# Flyback_Schematic.net
KiCad netlist of a schematic drawn in Altium Designer
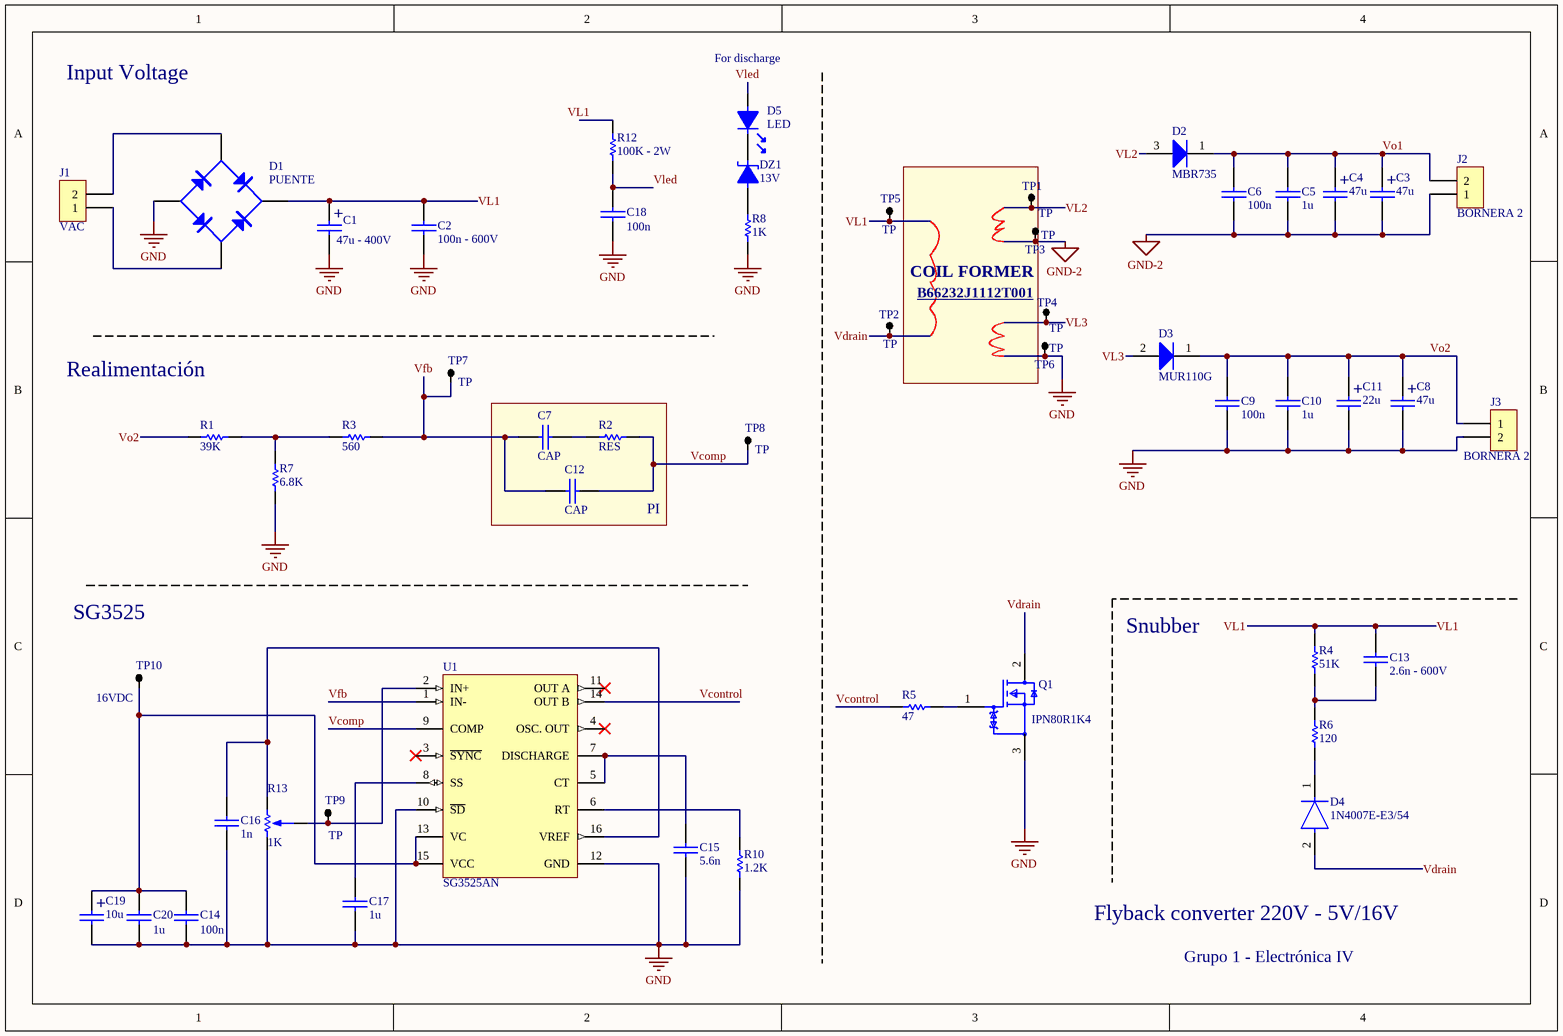
[diagram p0: Flyback_Schematic.SchDoc]

(export (version "E")
  (design (tool "Eeschema 10.0.6"))
  (components
    (comp (ref "C1")
      (value "47u - 400V")
      (footprint "CAP200RP2")
      (libsource (lib "LIBEBAL Tobi") (part "CAPPOL"))
    )
    (comp (ref "C2") (value "100n - 600V") (footprint "CAP200") (libsource (lib "LIBEBAL Tobi") (part "CAP")))
    (comp (ref "C3")
      (value "47u")
      (footprint "CAP100RP2")
      (description "Cerámico multicapa")
      (libsource (lib "LIBEBAL Tobi") (part "CAPPOL"))
    )
    (comp (ref "C4") (value "47u") (footprint "CAP100RP2") (libsource (lib "LIBEBAL Tobi") (part "CAPPOL")))
    (comp (ref "C5")
      (value "1u")
      (footprint "CAP100")
      (description "Cerámico multicapa")
      (libsource (lib "LIBEBAL Tobi") (part "CAP"))
    )
    (comp (ref "C6")
      (value "100n")
      (footprint "CAP100")
      (description "Cerámico multicapa")
      (libsource (lib "LIBEBAL Tobi") (part "CAP"))
    )
    (comp (ref "C7") (value "CAP") (footprint "0805") (libsource (lib "LIBEBAL Tobi") (part "CAP")))
    (comp (ref "C8") (value "47u") (footprint "CAP100RP2") (libsource (lib "LIBEBAL Tobi") (part "CAPPOL")))
    (comp (ref "C9")
      (value "100n")
      (footprint "CAP100")
      (description "Cerámico multicapa")
      (libsource (lib "LIBEBAL Tobi") (part "CAP"))
    )
    (comp (ref "C10")
      (value "1u")
      (footprint "CAP100")
      (description "Cerámico multicapa")
      (libsource (lib "LIBEBAL Tobi") (part "CAP"))
    )
    (comp (ref "C11") (value "22u") (footprint "CAP100RP2") (libsource (lib "LIBEBAL Tobi") (part "CAPPOL")))
    (comp (ref "C12") (value "CAP") (footprint "0805") (libsource (lib "LIBEBAL Tobi") (part "CAP")))
    (comp (ref "C13")
      (value "2.6n - 600V")
      (footprint "CAP200")
      (description "Tantalio")
      (libsource (lib "LIBEBAL Tobi") (part "CAP"))
    )
    (comp (ref "C14")
      (value "100n")
      (footprint "CAP100")
      (description "-10u Electronlitico - 1u Multicapa - 0.1u ceramico")
      (libsource (lib "LIBEBAL Tobi") (part "CAP"))
    )
    (comp (ref "C15") (value "5.6n") (footprint "0805") (libsource (lib "LIBEBAL Tobi") (part "CAP")))
    (comp (ref "C16") (value "1n") (footprint "0805") (libsource (lib "LIBEBAL Tobi") (part "CAP")))
    (comp (ref "C17") (value "1u") (footprint "0805") (libsource (lib "LIBEBAL Tobi") (part "CAP")))
    (comp (ref "C18") (value "100n") (footprint "0805") (libsource (lib "LIBEBAL Tobi") (part "CAP")))
    (comp (ref "C19") (value "10u") (footprint "CAP100RP") (libsource (lib "LIBEBAL Tobi") (part "CAPPOL")))
    (comp (ref "C20")
      (value "1u")
      (footprint "CAP200")
      (description "-10u Electronlitico - 1u Multicapa - 0.1u ceramico")
      (libsource (lib "LIBEBAL Tobi") (part "CAP"))
    )
    (comp (ref "D1")
      (value "PUENTE")
      (footprint "PUENTE - W10M")
      (libsource (lib "LIBEBAL Tobi") (part "PUENTE"))
    )
    (comp (ref "D2")
      (value "MBR735")
      (footprint "ONSC-TO-220-2-221B-04_E")
      (description "SWITCHMODE(TM) Power Rectifier, 2-Pin TO-220, Tube")
      (fields (field (name "MANUFACTURER") "On Semiconductor"))
      (libsource (lib "Altium Content Vault") (part "ONSC-D-K1A3-2_A"))
    )
    (comp (ref "D3")
      (value "MUR110G")
      (footprint "ONSC-AXIAL_LEAD-2-59-10_P")
      (description "SWITCHMODE(TM) Power Rectifier, 2-Pin Axial_Lead, Pb-Free, Bulk Bag")
      (fields (field (name "MANUFACTURER") "On Semiconductor") (field (name "PARTNUMBER") "MUR160G"))
      (libsource (lib "Altium Content Vault") (part "ONSC-D-K1A2-2"))
    )
    (comp (ref "D4")
      (value "1N4007E-E3/54")
      (footprint "FP-1N4007E-E3-54-MFG")
      (description "DIODE GEN PURP 1KV 1A DO204AL")
      (libsource (lib "Altium Content Vault") (part "d7152d700b627762746794eb795d46e"))
    )
    (comp (ref "D5") (value "LED") (footprint "LED3") (libsource (lib "LIBEBAL Tobi") (part "LED")))
    (comp (ref "DZ1") (value "13V") (footprint "DO41") (libsource (lib "LIBEBAL Tobi") (part "DIODO ZENER")))
    (comp (ref "J1") (value "VAC") (footprint "BORNERA2") (libsource (lib "") (part "BORNERA 2_1")))
    (comp (ref "J2") (value "BORNERA 2") (footprint "BORNERA2") (libsource (lib "") (part "BORNERA 2_2")))
    (comp (ref "J3")
      (value "BORNERA 2")
      (footprint "BORNERA2")
      (libsource (lib "LIBEBAL Tobi") (part "BORNERA 2"))
    )
    (comp (ref "Q1")
      (value "IPN80R1K4")
      (footprint "FP-PG-SOT223-3-MFG")
      (description "IPN80R1K4P7ATMA1 Power Transistor MOSFET N-Channel Enhancement 800V 4A 3-Pin SOT-223")
      (libsource (lib "Altium Content Vault") (part "d2f4479c20ac9ad0f88d1bd240a35b2"))
    )
    (comp (ref "R1") (value "39K") (footprint "0805") (libsource (lib "LIBEBAL Tobi") (part "RES")))
    (comp (ref "R2") (value "RES") (footprint "0805") (libsource (lib "LIBEBAL Tobi") (part "RES")))
    (comp (ref "R3") (value "560") (footprint "0805") (libsource (lib "LIBEBAL Tobi") (part "RES")))
    (comp (ref "R4") (value "51K") (footprint "RES600") (libsource (lib "LIBEBAL Tobi") (part "RES")))
    (comp (ref "R5") (value "47") (footprint "RES300") (libsource (lib "LIBEBAL Tobi") (part "RES")))
    (comp (ref "R6") (value "120") (footprint "RES400") (libsource (lib "LIBEBAL Tobi") (part "RES")))
    (comp (ref "R7") (value "6.8K") (footprint "0805") (libsource (lib "LIBEBAL Tobi") (part "RES")))
    (comp (ref "R8") (value "1K") (footprint "0805") (libsource (lib "LIBEBAL") (part "RES")))
    (comp (ref "R10") (value "1.2K") (footprint "0805") (libsource (lib "LIBEBAL Tobi") (part "RES")))
    (comp (ref "R12") (value "100K - 2W") (footprint "RES300") (libsource (lib "LIBEBAL Tobi") (part "RES")))
    (comp (ref "R13") (value "1K") (footprint "PRESET V") (libsource (lib "LIBEBAL Tobi") (part "PRESET")))
    (comp (ref "TP1") (value "TP") (footprint "TPTH") (libsource (lib "LIBEBAL") (part "TP")))
    (comp (ref "TP2") (value "TP") (footprint "TPTH") (libsource (lib "LIBEBAL") (part "TP")))
    (comp (ref "TP3") (value "TP") (footprint "TPTH") (libsource (lib "LIBEBAL") (part "TP")))
    (comp (ref "TP4") (value "TP") (footprint "TPTH") (libsource (lib "LIBEBAL") (part "TP")))
    (comp (ref "TP5") (value "TP") (footprint "TPTH") (libsource (lib "LIBEBAL") (part "TP")))
    (comp (ref "TP6") (value "TP") (footprint "TPTH") (libsource (lib "LIBEBAL") (part "TP")))
    (comp (ref "TP7") (value "TP") (footprint "TPTH") (libsource (lib "LIBEBAL Tobi") (part "TP")))
    (comp (ref "TP8") (value "TP") (footprint "TPTH") (libsource (lib "LIBEBAL Tobi") (part "TP")))
    (comp (ref "TP9") (value "TP") (footprint "TPTH") (libsource (lib "LIBEBAL Tobi") (part "TP")))
    (comp (ref "TP10") (value "16VDC") (footprint "TPTH") (libsource (lib "LIBEBAL Tobi") (part "TP")))
    (comp (ref "U1")
      (value "SG3525AN")
      (footprint "ONSC-PDIP-16-648-08_T")
      (description "Pulse Width Modulator Control Circuit, 8 to 35 V, 0 to 70 degC, 16-Pin PDIP, RoHS, Tube")
      (fields (field (name "MANUFACTURER") "ON Semiconductor"))
      (libsource (lib "Altium Content Vault") (part "ONSC-SG3525A-SOIC_PDIP-16"))
    )
  )
  (nets
    (net (code "1") (name "/VL1") (class "Default")
      (node (ref "C1") (pin "1") (pinfunction "1_1") (pintype "passive"))
      (node (ref "C13") (pin "2") (pinfunction "2_2") (pintype "passive"))
      (node (ref "C2") (pin "1") (pinfunction "1_1") (pintype "passive"))
      (node (ref "D1") (pin "1") (pinfunction "V+_1") (pintype "passive"))
      (node (ref "R12") (pin "2") (pinfunction "2_2") (pintype "passive"))
      (node (ref "R4") (pin "2") (pinfunction "2_2") (pintype "passive"))
      (node (ref "TP5") (pin "1") (pinfunction "1_1") (pintype "passive"))
    )
    (net (code "2") (name "/VL2") (class "Default")
      (node (ref "D2") (pin "3") (pinfunction "A_3") (pintype "passive"))
      (node (ref "TP1") (pin "1") (pinfunction "1_1") (pintype "passive"))
    )
    (net (code "3") (name "/VL3") (class "Default")
      (node (ref "D3") (pin "2") (pinfunction "A_2") (pintype "passive"))
      (node (ref "TP4") (pin "1") (pinfunction "1_1") (pintype "passive"))
    )
    (net (code "4") (name "/Vcomp") (class "Default")
      (node (ref "C12") (pin "2") (pinfunction "2_2") (pintype "passive"))
      (node (ref "R2") (pin "2") (pinfunction "2_2") (pintype "passive"))
      (node (ref "TP8") (pin "1") (pinfunction "1_1") (pintype "passive"))
      (node (ref "U1") (pin "9") (pinfunction "COMP_9") (pintype "passive"))
    )
    (net (code "5") (name "/Vcontrol") (class "Default")
      (node (ref "R5") (pin "1") (pinfunction "1_1") (pintype "passive"))
      (node (ref "U1") (pin "14") (pinfunction "OUT_B_14") (pintype "output"))
    )
    (net (code "6") (name "/Vdrain") (class "Default")
      (node (ref "D4") (pin "2") (pinfunction "A_2") (pintype "passive"))
      (node (ref "Q1") (pin "2") (pinfunction "D_2") (pintype "passive"))
      (node (ref "TP2") (pin "1") (pinfunction "1_1") (pintype "passive"))
    )
    (net (code "7") (name "/Vfb") (class "Default")
      (node (ref "C12") (pin "1") (pinfunction "1_1") (pintype "passive"))
      (node (ref "C7") (pin "2") (pinfunction "2_2") (pintype "passive"))
      (node (ref "R3") (pin "1") (pinfunction "1_1") (pintype "passive"))
      (node (ref "TP7") (pin "1") (pinfunction "1_1") (pintype "passive"))
      (node (ref "U1") (pin "1") (pinfunction "IN-_1") (pintype "input"))
    )
    (net (code "8") (name "/Vled") (class "Default")
      (node (ref "C18") (pin "2") (pinfunction "2_2") (pintype "passive"))
      (node (ref "D5") (pin "1") (pinfunction "1_1") (pintype "passive"))
      (node (ref "R12") (pin "1") (pinfunction "1_1") (pintype "passive"))
    )
    (net (code "9") (name "/Vo1") (class "Default")
      (node (ref "C3") (pin "1") (pinfunction "1_1") (pintype "passive"))
      (node (ref "C4") (pin "1") (pinfunction "1_1") (pintype "passive"))
      (node (ref "C5") (pin "1") (pinfunction "1_1") (pintype "passive"))
      (node (ref "C6") (pin "1") (pinfunction "1_1") (pintype "passive"))
      (node (ref "D2") (pin "1") (pinfunction "K_1") (pintype "passive"))
      (node (ref "J2") (pin "2") (pinfunction "2_2") (pintype "passive"))
    )
    (net (code "10") (name "/Vo2") (class "Default")
      (node (ref "C10") (pin "1") (pinfunction "1_1") (pintype "passive"))
      (node (ref "C11") (pin "1") (pinfunction "1_1") (pintype "passive"))
      (node (ref "C8") (pin "1") (pinfunction "1_1") (pintype "passive"))
      (node (ref "C9") (pin "1") (pinfunction "1_1") (pintype "passive"))
      (node (ref "D3") (pin "1") (pinfunction "K_1") (pintype "passive"))
      (node (ref "J3") (pin "1") (pinfunction "1_1") (pintype "passive"))
      (node (ref "R1") (pin "2") (pinfunction "2_2") (pintype "passive"))
    )
    (net (code "11") (name "GND") (class "Default")
      (node (ref "C1") (pin "2") (pinfunction "2_2") (pintype "passive"))
      (node (ref "C10") (pin "2") (pinfunction "2_2") (pintype "passive"))
      (node (ref "C11") (pin "2") (pinfunction "2_2") (pintype "passive"))
      (node (ref "C14") (pin "1") (pinfunction "1_1") (pintype "passive"))
      (node (ref "C15") (pin "2") (pinfunction "2_2") (pintype "passive"))
      (node (ref "C16") (pin "1") (pinfunction "1_1") (pintype "passive"))
      (node (ref "C17") (pin "2") (pinfunction "2_2") (pintype "passive"))
      (node (ref "C18") (pin "1") (pinfunction "1_1") (pintype "passive"))
      (node (ref "C19") (pin "2") (pinfunction "2_2") (pintype "passive"))
      (node (ref "C2") (pin "2") (pinfunction "2_2") (pintype "passive"))
      (node (ref "C20") (pin "1") (pinfunction "1_1") (pintype "passive"))
      (node (ref "C8") (pin "2") (pinfunction "2_2") (pintype "passive"))
      (node (ref "C9") (pin "2") (pinfunction "2_2") (pintype "passive"))
      (node (ref "D1") (pin "3") (pinfunction "V-_3") (pintype "passive"))
      (node (ref "J3") (pin "2") (pinfunction "2_2") (pintype "passive"))
      (node (ref "Q1") (pin "3") (pinfunction "S_3") (pintype "passive"))
      (node (ref "R10") (pin "2") (pinfunction "2_2") (pintype "passive"))
      (node (ref "R13") (pin "3") (pinfunction "3_3") (pintype "passive"))
      (node (ref "R7") (pin "2") (pinfunction "2_2") (pintype "passive"))
      (node (ref "R8") (pin "2") (pinfunction "2_2") (pintype "passive"))
      (node (ref "TP6") (pin "1") (pinfunction "1_1") (pintype "passive"))
      (node (ref "U1") (pin "10") (pinfunction "~{SD}_10") (pintype "input"))
      (node (ref "U1") (pin "12") (pinfunction "GND_12") (pintype "power_in"))
    )
    (net (code "12") (name "GND-2") (class "Default")
      (node (ref "C3") (pin "2") (pinfunction "2_2") (pintype "passive"))
      (node (ref "C4") (pin "2") (pinfunction "2_2") (pintype "passive"))
      (node (ref "C5") (pin "2") (pinfunction "2_2") (pintype "passive"))
      (node (ref "C6") (pin "2") (pinfunction "2_2") (pintype "passive"))
      (node (ref "J2") (pin "1") (pinfunction "1_1") (pintype "passive"))
      (node (ref "TP3") (pin "1") (pinfunction "1_1") (pintype "passive"))
    )
    (net (code "13") (name "Net-(C7-Pad1)") (class "Default")
      (node (ref "C7") (pin "1") (pinfunction "1_1") (pintype "passive"))
      (node (ref "R2") (pin "1") (pinfunction "1_1") (pintype "passive"))
    )
    (net (code "14") (name "Net-(C13-Pad1)") (class "Default")
      (node (ref "C13") (pin "1") (pinfunction "1_1") (pintype "passive"))
      (node (ref "R4") (pin "1") (pinfunction "1_1") (pintype "passive"))
      (node (ref "R6") (pin "2") (pinfunction "2_2") (pintype "passive"))
    )
    (net (code "15") (name "Net-(D1-AC-Pad2)") (class "Default")
      (node (ref "D1") (pin "2") (pinfunction "AC_2") (pintype "passive"))
      (node (ref "J1") (pin "2") (pinfunction "2_2") (pintype "passive"))
    )
    (net (code "16") (name "Net-(D1-AC-Pad4)") (class "Default")
      (node (ref "D1") (pin "4") (pinfunction "AC_4") (pintype "passive"))
      (node (ref "J1") (pin "1") (pinfunction "1_1") (pintype "passive"))
    )
    (net (code "17") (name "Net-(D4-C)") (class "Default")
      (node (ref "D4") (pin "1") (pinfunction "C_1") (pintype "passive"))
      (node (ref "R6") (pin "1") (pinfunction "1_1") (pintype "passive"))
    )
    (net (code "18") (name "Net-(D5-Pad2)") (class "Default")
      (node (ref "D5") (pin "2") (pinfunction "2_2") (pintype "passive"))
      (node (ref "DZ1") (pin "2") (pinfunction "2_2") (pintype "passive"))
    )
    (net (code "19") (name "Net-(DZ1-Pad1)") (class "Default")
      (node (ref "DZ1") (pin "1") (pinfunction "1_1") (pintype "passive"))
      (node (ref "R8") (pin "1") (pinfunction "1_1") (pintype "passive"))
    )
    (net (code "20") (name "Net-(Q1-G)") (class "Default")
      (node (ref "Q1") (pin "1") (pinfunction "G_1") (pintype "passive"))
      (node (ref "R5") (pin "2") (pinfunction "2_2") (pintype "passive"))
    )
    (net (code "21") (name "Net-(R1-Pad1)") (class "Default")
      (node (ref "R1") (pin "1") (pinfunction "1_1") (pintype "passive"))
      (node (ref "R3") (pin "2") (pinfunction "2_2") (pintype "passive"))
      (node (ref "R7") (pin "1") (pinfunction "1_1") (pintype "passive"))
    )
    (net (code "22") (name "Net-(U1-CT)") (class "Default")
      (node (ref "C15") (pin "1") (pinfunction "1_1") (pintype "passive"))
      (node (ref "U1") (pin "5") (pinfunction "CT_5") (pintype "passive"))
      (node (ref "U1") (pin "7") (pinfunction "DISCHARGE_7") (pintype "open_collector"))
    )
    (net (code "23") (name "Net-(U1-IN+)") (class "Default")
      (node (ref "R13") (pin "2") (pinfunction "2_2") (pintype "passive"))
      (node (ref "TP9") (pin "1") (pinfunction "1_1") (pintype "passive"))
      (node (ref "U1") (pin "2") (pinfunction "IN+_2") (pintype "input"))
    )
    (net (code "24") (name "Net-(U1-RT)") (class "Default")
      (node (ref "R10") (pin "1") (pinfunction "1_1") (pintype "passive"))
      (node (ref "U1") (pin "6") (pinfunction "RT_6") (pintype "passive"))
    )
    (net (code "25") (name "Net-(U1-SS)") (class "Default")
      (node (ref "C17") (pin "1") (pinfunction "1_1") (pintype "passive"))
      (node (ref "U1") (pin "8") (pinfunction "SS_8") (pintype "bidirectional"))
    )
    (net (code "26") (name "Net-(U1-VC)") (class "Default")
      (node (ref "C14") (pin "2") (pinfunction "2_2") (pintype "passive"))
      (node (ref "C19") (pin "1") (pinfunction "1_1") (pintype "passive"))
      (node (ref "C20") (pin "2") (pinfunction "2_2") (pintype "passive"))
      (node (ref "TP10") (pin "1") (pinfunction "1_1") (pintype "passive"))
      (node (ref "U1") (pin "13") (pinfunction "VC_13") (pintype "power_in"))
      (node (ref "U1") (pin "15") (pinfunction "VCC_15") (pintype "power_in"))
    )
    (net (code "27") (name "Net-(U1-VREF)") (class "Default")
      (node (ref "C16") (pin "2") (pinfunction "2_2") (pintype "passive"))
      (node (ref "R13") (pin "1") (pinfunction "1_1") (pintype "passive"))
      (node (ref "U1") (pin "16") (pinfunction "VREF_16") (pintype "output"))
    )
    (net (code "28") (name "unconnected-(U1-OSC._OUT-Pad4)") (class "Default")
      (node (ref "U1") (pin "4") (pinfunction "OSC._OUT_4") (pintype "output+no_connect"))
    )
    (net (code "29") (name "unconnected-(U1-OUT_A-Pad11)") (class "Default")
      (node (ref "U1") (pin "11") (pinfunction "OUT_A_11") (pintype "output+no_connect"))
    )
    (net (code "30") (name "unconnected-(U1-~{SYNC}-Pad3)") (class "Default")
      (node (ref "U1") (pin "3") (pinfunction "~{SYNC}_3") (pintype "input+no_connect"))
    )
  )
)
